# pca20035_sheet5_power_supply.net
KiCad netlist of a schematic drawn in Altium Designer
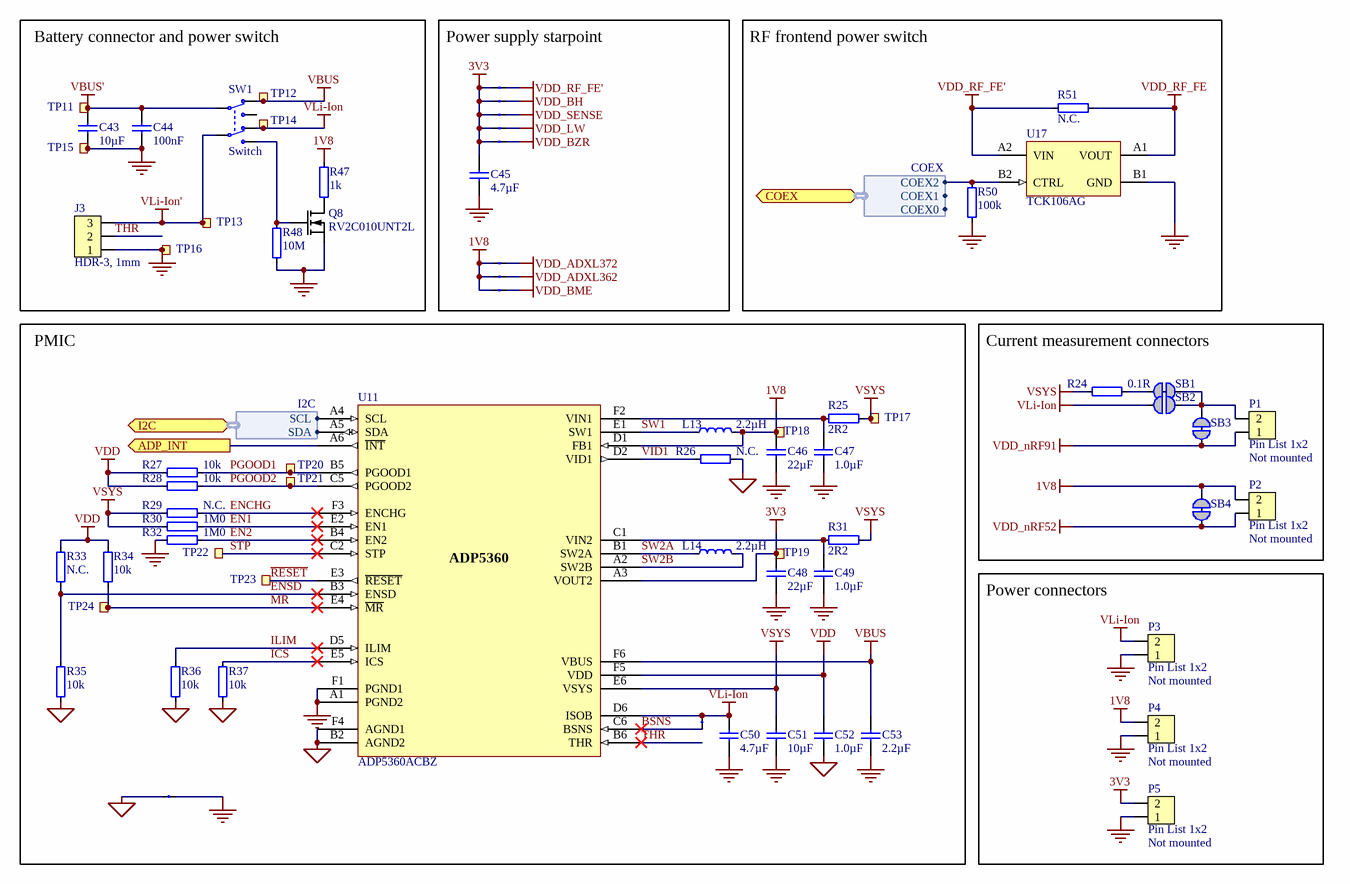
[diagram p0: pca20035_sheet5_power_supply.SchDoc]

(export (version "E")
  (design (tool "Eeschema 10.0.6"))
  (components
    (comp (ref "C43")
      (value "10µF")
      (footprint "CAPC1608X06L")
      (description "Capacitor, X5R, ±20%")
      (fields (field (name "PART NUMBER") "C0603-10µ") (field (name "MANUFACTURER") "N.A."))
      (libsource (lib "AltiumLib") (part "CAP"))
    )
    (comp (ref "C44")
      (value "100nF")
      (footprint "CAPC0603X03L_C")
      (description "Capacitor, X5R, ±10%")
      (fields (field (name "PART NUMBER") "C0201-100n") (field (name "MANUFACTURER") "N.A."))
      (libsource (lib "AltiumLib") (part "CAP"))
    )
    (comp (ref "C45")
      (value "4.7µF")
      (footprint "CAPC1608X06L")
      (description "Capacitor, X5R, ±10%")
      (fields (field (name "PART NUMBER") "C0603-4µ7") (field (name "MANUFACTURER") "N.A."))
      (libsource (lib "AltiumLib") (part "CAP"))
    )
    (comp (ref "C46")
      (value "22µF")
      (footprint "CAPC1608X06L")
      (description "Capacitor, X5R, ±20%, 6.3V")
      (fields
        (field (name "PART NUMBER") "C0603-22µ-6.3V")
        (field (name "MANUFACTURER") "Samsung Electro-Mechanics America")
      )
      (libsource (lib "AltiumLib") (part "CAP"))
    )
    (comp (ref "C47")
      (value "1.0µF")
      (footprint "CAPC1005X04L")
      (description "Capacitor, X5R, ±5%, 6.3V")
      (fields (field (name "PART NUMBER") "C0402-1µ0") (field (name "MANUFACTURER") "N.A."))
      (libsource (lib "AltiumLib") (part "CAP"))
    )
    (comp (ref "C48")
      (value "22µF")
      (footprint "CAPC1608X06L")
      (description "Capacitor, X5R, ±20%, 6.3V")
      (fields
        (field (name "PART NUMBER") "C0603-22µ-6.3V")
        (field (name "MANUFACTURER") "Samsung Electro-Mechanics America")
      )
      (libsource (lib "AltiumLib") (part "CAP"))
    )
    (comp (ref "C49")
      (value "1.0µF")
      (footprint "CAPC1608X06L")
      (description "Capacitor, X7R, ±10%")
      (fields (field (name "PART NUMBER") "C0603-1µ0") (field (name "MANUFACTURER") "N.A."))
      (libsource (lib "AltiumLib") (part "CAP"))
    )
    (comp (ref "C50")
      (value "4.7µF")
      (footprint "CAPC1608X06L")
      (description "Capacitor, X5R, ±10%")
      (fields (field (name "PART NUMBER") "C0603-4µ7") (field (name "MANUFACTURER") "N.A."))
      (libsource (lib "AltiumLib") (part "CAP"))
    )
    (comp (ref "C51")
      (value "10µF")
      (footprint "CAPC1608X06L")
      (description "Capacitor, X5R, ±20%")
      (fields (field (name "PART NUMBER") "C0603-10µ") (field (name "MANUFACTURER") "N.A."))
      (libsource (lib "AltiumLib") (part "CAP"))
    )
    (comp (ref "C52")
      (value "1.0µF")
      (footprint "CAPC1005X04L")
      (description "Capacitor, X5R, ±5%, 6.3V")
      (fields (field (name "PART NUMBER") "C0402-1µ0") (field (name "MANUFACTURER") "N.A."))
      (libsource (lib "AltiumLib") (part "CAP"))
    )
    (comp (ref "C53")
      (value "2.2µF")
      (footprint "CAPC1608X06L")
      (description "Capacitor, X7R, ±10%, 10V")
      (fields
        (field (name "PART NUMBER") "C0603-2µ2-10V")
        (field (name "MANUFACTURER") "Samsung Electro-Mechanics America")
      )
      (libsource (lib "AltiumLib") (part "CAP"))
    )
    (comp (ref "J3")
      (value "HDR-3, 1mm")
      (footprint "SM03B-SRSS-TB")
      (description "1.0mm pitch connector side entry SMD")
      (fields
        (field (name "PART NUMBER") "SM03B-SRSS-TB")
        (field (name "MANUFACTURER") "JST Sales America Inc.")
      )
      (libsource (lib "AltiumLib") (part "CONN-3"))
    )
    (comp (ref "L13")
      (value "2.2µH")
      (footprint "INDC2016X18N")
      (description "Shielded Multilayer Inductor, 1.2A, ±20%, 110mOhm, Q=10 @ 1MHz")
      (fields
        (field (name "PART NUMBER") "L0806-2µ2-1.2A-110mOhm")
        (field (name "MANUFACTURER") "Wurth Elektronik")
      )
      (libsource (lib "AltiumLib") (part "IND"))
    )
    (comp (ref "L14")
      (value "2.2µH")
      (footprint "INDC2016X18N")
      (description "Shielded Multilayer Inductor, 1.2A, ±20%, 110mOhm, Q=10 @ 1MHz")
      (fields
        (field (name "PART NUMBER") "L0806-2µ2-1.2A-110mOhm")
        (field (name "MANUFACTURER") "Wurth Elektronik")
      )
      (libsource (lib "AltiumLib") (part "IND"))
    )
    (comp (ref "P1")
      (value "Pin List 1x2")
      (footprint "LIST_1x2-NC")
      (description "Pin List 1x2, 2.54mm (100mil)")
      (fields
        (field (name "PART NUMBER") "Pin List 1x2, N.C.")
        (field (name "ASSEMBLY") "Not mounted")
        (field (name "MANUFACTURER") "N.A.")
      )
      (libsource (lib "AltiumLib") (part "CONN-2"))
    )
    (comp (ref "P2")
      (value "Pin List 1x2")
      (footprint "LIST_1x2-NC")
      (description "Pin List 1x2, 2.54mm (100mil)")
      (fields
        (field (name "PART NUMBER") "Pin List 1x2, N.C.")
        (field (name "ASSEMBLY") "Not mounted")
        (field (name "MANUFACTURER") "N.A.")
      )
      (libsource (lib "AltiumLib") (part "CONN-2"))
    )
    (comp (ref "P3")
      (value "Pin List 1x2")
      (footprint "LIST_1x2-NC")
      (description "Pin List 1x2, 2.54mm (100mil)")
      (fields
        (field (name "PART NUMBER") "Pin List 1x2, N.C.")
        (field (name "ASSEMBLY") "Not mounted")
        (field (name "MANUFACTURER") "N.A.")
      )
      (libsource (lib "AltiumLib") (part "CONN-2"))
    )
    (comp (ref "P4")
      (value "Pin List 1x2")
      (footprint "LIST_1x2-NC")
      (description "Pin List 1x2, 2.54mm (100mil)")
      (fields
        (field (name "PART NUMBER") "Pin List 1x2, N.C.")
        (field (name "ASSEMBLY") "Not mounted")
        (field (name "MANUFACTURER") "N.A.")
      )
      (libsource (lib "AltiumLib") (part "CONN-2"))
    )
    (comp (ref "P5")
      (value "Pin List 1x2")
      (footprint "LIST_1x2-NC")
      (description "Pin List 1x2, 2.54mm (100mil)")
      (fields
        (field (name "PART NUMBER") "Pin List 1x2, N.C.")
        (field (name "ASSEMBLY") "Not mounted")
        (field (name "MANUFACTURER") "N.A.")
      )
      (libsource (lib "AltiumLib") (part "CONN-2"))
    )
    (comp (ref "Q8")
      (value "RV2C010UNT2L")
      (footprint "DFN65P100X40-3L")
      (description "N-Channel MOSFET, 20V, 1A, 470mOhm, 400mW")
      (fields (field (name "MANUFACTURER") "Rohm Semiconductor"))
      (libsource (lib "AltiumLib") (part "T{colon}FET-N"))
    )
    (comp (ref "R24")
      (value "0.1R")
      (footprint "RESC1005X04L")
      (description "Resistor, ±1%, 0.063W")
      (fields (field (name "PART NUMBER") "R0402-0R1") (field (name "MANUFACTURER") "N.A."))
      (libsource (lib "AltiumLib") (part "RES"))
    )
    (comp (ref "R25")
      (value "2R2")
      (footprint "RESC1005X04L")
      (description "Resistor, ±1%, 0.063W")
      (fields (field (name "PART NUMBER") "R0402-2R2") (field (name "MANUFACTURER") "N.A."))
      (libsource (lib "AltiumLib") (part "RES"))
    )
    (comp (ref "R26")
      (value "N.C.")
      (footprint "RESC0603X03L_C_NC")
      (description "Not mounted")
      (fields (field (name "PART NUMBER") "R0201-N.C.") (field (name "MANUFACTURER") "N.A."))
      (libsource (lib "AltiumLib") (part "RES"))
    )
    (comp (ref "R27")
      (value "10k")
      (footprint "RESC0603X03L_C")
      (description "Resistor, ±1%, 0.05W")
      (fields (field (name "PART NUMBER") "R0201-10k") (field (name "MANUFACTURER") "N.A."))
      (libsource (lib "AltiumLib") (part "RES"))
    )
    (comp (ref "R28")
      (value "10k")
      (footprint "RESC0603X03L_C")
      (description "Resistor, ±1%, 0.05W")
      (fields (field (name "PART NUMBER") "R0201-10k") (field (name "MANUFACTURER") "N.A."))
      (libsource (lib "AltiumLib") (part "RES"))
    )
    (comp (ref "R29")
      (value "N.C.")
      (footprint "RESC0603X03L_C_NC")
      (description "Not mounted")
      (fields (field (name "PART NUMBER") "R0201-N.C.") (field (name "MANUFACTURER") "N.A."))
      (libsource (lib "AltiumLib") (part "RES"))
    )
    (comp (ref "R30")
      (value "1M0")
      (footprint "RESC0603X03L_C")
      (description "Resistor, ±1%, 0.05W")
      (fields (field (name "PART NUMBER") "R0201-1M0") (field (name "MANUFACTURER") "N.A."))
      (libsource (lib "AltiumLib") (part "RES"))
    )
    (comp (ref "R31")
      (value "2R2")
      (footprint "RESC1005X04L")
      (description "Resistor, ±1%, 0.063W")
      (fields (field (name "PART NUMBER") "R0402-2R2") (field (name "MANUFACTURER") "N.A."))
      (libsource (lib "AltiumLib") (part "RES"))
    )
    (comp (ref "R32")
      (value "1M0")
      (footprint "RESC0603X03L_C")
      (description "Resistor, ±1%, 0.05W")
      (fields (field (name "PART NUMBER") "R0201-1M0") (field (name "MANUFACTURER") "N.A."))
      (libsource (lib "AltiumLib") (part "RES"))
    )
    (comp (ref "R33")
      (value "N.C.")
      (footprint "RESC0603X03L_C_NC")
      (description "Not mounted")
      (fields (field (name "PART NUMBER") "R0201-N.C.") (field (name "MANUFACTURER") "N.A."))
      (libsource (lib "AltiumLib") (part "RES"))
    )
    (comp (ref "R34")
      (value "10k")
      (footprint "RESC0603X03L_C")
      (description "Resistor, ±1%, 0.05W")
      (fields (field (name "PART NUMBER") "R0201-10k") (field (name "MANUFACTURER") "N.A."))
      (libsource (lib "AltiumLib") (part "RES"))
    )
    (comp (ref "R35")
      (value "10k")
      (footprint "RESC0603X03L_C")
      (description "Resistor, ±1%, 0.05W")
      (fields (field (name "PART NUMBER") "R0201-10k") (field (name "MANUFACTURER") "N.A."))
      (libsource (lib "AltiumLib") (part "RES"))
    )
    (comp (ref "R36")
      (value "10k")
      (footprint "RESC0603X03L_C")
      (description "Resistor, ±1%, 0.05W")
      (fields (field (name "PART NUMBER") "R0201-10k") (field (name "MANUFACTURER") "N.A."))
      (libsource (lib "AltiumLib") (part "RES"))
    )
    (comp (ref "R37")
      (value "10k")
      (footprint "RESC0603X03L_C")
      (description "Resistor, ±1%, 0.05W")
      (fields (field (name "PART NUMBER") "R0201-10k") (field (name "MANUFACTURER") "N.A."))
      (libsource (lib "AltiumLib") (part "RES"))
    )
    (comp (ref "R47")
      (value "1k")
      (footprint "RESC0603X03L_C")
      (description "Resistor, ±1%, 0.05W")
      (fields (field (name "PART NUMBER") "R0201-1k0") (field (name "MANUFACTURER") "N.A."))
      (libsource (lib "AltiumLib") (part "RES"))
    )
    (comp (ref "R48")
      (value "10M")
      (footprint "RESC0603X03L_C")
      (description "Resistor, ±1%, 0.05W")
      (fields (field (name "PART NUMBER") "R0201-10M") (field (name "MANUFACTURER") "N.A."))
      (libsource (lib "AltiumLib") (part "RES"))
    )
    (comp (ref "R50")
      (value "100k")
      (footprint "RESC0603X03L_C")
      (description "Resistor, ±1%, 0.05W")
      (fields (field (name "PART NUMBER") "R0201-100k") (field (name "MANUFACTURER") "N.A."))
      (libsource (lib "AltiumLib") (part "RES"))
    )
    (comp (ref "R51")
      (value "N.C.")
      (footprint "RESC0603X03L_C_NC")
      (description "Not mounted")
      (fields (field (name "PART NUMBER") "R0201-N.C.") (field (name "MANUFACTURER") "N.A."))
      (libsource (lib "AltiumLib") (part "RES"))
    )
    (comp (ref "SB1")
      (value "Solderbridge")
      (footprint "Solderbridge_Shorted")
      (description "Shorted Solderbridge")
      (fields (field (name "PART NUMBER") "Solderbridge Shorted") (field (name "MANUFACTURER") "N.A."))
      (libsource (lib "AltiumLib") (part "SOLDERBRIDGE_SHORTED"))
    )
    (comp (ref "SB2")
      (value "Solderbridge")
      (footprint "Solderbridge")
      (fields (field (name "MANUFACTURER") "N.A."))
      (libsource (lib "AltiumLib") (part "SOLDERBRIDGE"))
    )
    (comp (ref "SB3")
      (value "Solderbridge")
      (footprint "Solderbridge_Shorted")
      (description "Shorted Solderbridge")
      (fields (field (name "PART NUMBER") "Solderbridge Shorted") (field (name "MANUFACTURER") "N.A."))
      (libsource (lib "AltiumLib") (part "SOLDERBRIDGE_SHORTED"))
    )
    (comp (ref "SB4")
      (value "Solderbridge")
      (footprint "Solderbridge_Shorted")
      (description "Shorted Solderbridge")
      (fields (field (name "PART NUMBER") "Solderbridge Shorted") (field (name "MANUFACTURER") "N.A."))
      (libsource (lib "AltiumLib") (part "SOLDERBRIDGE_SHORTED"))
    )
    (comp (ref "ST1")
      (value "N.A.")
      (footprint "2 PIN STARPOINT")
      (description "Starpoint")
      (fields (field (name "PART NUMBER") "2 pin starpoint"))
      (libsource (lib "AltiumLib") (part "2 pin starpoint"))
    )
    (comp (ref "ST2")
      (value "N.A.")
      (footprint "2 PIN STARPOINT")
      (description "Starpoint")
      (fields (field (name "PART NUMBER") "2 pin starpoint"))
      (libsource (lib "AltiumLib") (part "2 pin starpoint"))
    )
    (comp (ref "ST3")
      (value "N.A.")
      (footprint "2 PIN STARPOINT")
      (description "Starpoint")
      (fields (field (name "PART NUMBER") "2 pin starpoint"))
      (libsource (lib "AltiumLib") (part "2 pin starpoint"))
    )
    (comp (ref "ST4")
      (value "N.A.")
      (footprint "2 PIN STARPOINT")
      (description "Starpoint")
      (fields (field (name "PART NUMBER") "2 pin starpoint"))
      (libsource (lib "AltiumLib") (part "2 pin starpoint"))
    )
    (comp (ref "ST5")
      (value "N.A.")
      (footprint "2 PIN STARPOINT")
      (description "Starpoint")
      (fields (field (name "PART NUMBER") "2 pin starpoint"))
      (libsource (lib "AltiumLib") (part "2 pin starpoint"))
    )
    (comp (ref "ST7")
      (value "N.A.")
      (footprint "2 PIN STARPOINT")
      (description "Starpoint")
      (fields (field (name "PART NUMBER") "2 pin starpoint"))
      (libsource (lib "AltiumLib") (part "2 pin starpoint"))
    )
    (comp (ref "ST8")
      (value "N.A.")
      (footprint "2 PIN STARPOINT")
      (description "Starpoint")
      (fields (field (name "PART NUMBER") "2 pin starpoint"))
      (libsource (lib "AltiumLib") (part "2 pin starpoint"))
    )
    (comp (ref "ST9")
      (value "N.A.")
      (footprint "2 PIN STARPOINT")
      (description "Starpoint")
      (fields (field (name "PART NUMBER") "2 pin starpoint"))
      (libsource (lib "AltiumLib") (part "2 pin starpoint"))
    )
    (comp (ref "ST10")
      (value "N.A.")
      (footprint "2 PIN STARPOINT")
      (description "Starpoint")
      (fields (field (name "PART NUMBER") "2 pin starpoint"))
      (libsource (lib "AltiumLib") (part "2 pin starpoint"))
    )
    (comp (ref "ST11")
      (value "N.A.")
      (footprint "2 PIN STARPOINT")
      (description "Starpoint")
      (fields (field (name "PART NUMBER") "2 pin starpoint"))
      (libsource (lib "AltiumLib") (part "2 pin starpoint"))
    )
    (comp (ref "SW1")
      (value "Switch")
      (footprint "Switch-Slide-RA-J-Lead-DPDT-8.5x3.5mm")
      (description "SMD slide Switch (ON-ON)")
      (fields
        (field (name "PART NUMBER") "Switch-Slide-RA-J-Lead-DPDT-8.5x3.5mm_Copal")
        (field (name "MANUFACTURER") "Copal Electronics Inc")
      )
      (libsource (lib "AltiumLib") (part "SW-DPDT"))
    )
    (comp (ref "TP11")
      (value "Ø1.5mm,SMD")
      (footprint "TP_SMD_Ø1.5mm")
      (description "1.5mm circular SMD testpad")
      (fields
        (field (name "PART NUMBER") "TP_SMD_Ø1.5MM")
        (field (name "MANUFACTURER") "Nordic Semiconductor")
      )
      (libsource (lib "AltiumLib") (part "TESTPAD"))
    )
    (comp (ref "TP12")
      (value "Ø1.5mm,SMD")
      (footprint "TP_SMD_Ø1.5mm")
      (description "1.5mm circular SMD testpad")
      (fields
        (field (name "PART NUMBER") "TP_SMD_Ø1.5MM")
        (field (name "MANUFACTURER") "Nordic Semiconductor")
      )
      (libsource (lib "") (part "TESTPAD_2"))
    )
    (comp (ref "TP13")
      (value "Ø1.5mm,SMD")
      (footprint "TP_SMD_Ø1.5mm")
      (description "1.5mm circular SMD testpad")
      (fields
        (field (name "PART NUMBER") "TP_SMD_Ø1.5MM")
        (field (name "MANUFACTURER") "Nordic Semiconductor")
      )
      (libsource (lib "") (part "TESTPAD_1"))
    )
    (comp (ref "TP14")
      (value "Ø1.5mm,SMD")
      (footprint "TP_SMD_Ø1.5mm")
      (description "1.5mm circular SMD testpad")
      (fields
        (field (name "PART NUMBER") "TP_SMD_Ø1.5MM")
        (field (name "MANUFACTURER") "Nordic Semiconductor")
      )
      (libsource (lib "") (part "TESTPAD_2"))
    )
    (comp (ref "TP15")
      (value "Ø1.5mm,SMD")
      (footprint "TP_SMD_Ø1.5mm")
      (description "1.5mm circular SMD testpad")
      (fields
        (field (name "PART NUMBER") "TP_SMD_Ø1.5MM")
        (field (name "MANUFACTURER") "Nordic Semiconductor")
      )
      (libsource (lib "AltiumLib") (part "TESTPAD"))
    )
    (comp (ref "TP16")
      (value "Ø1.5mm,SMD")
      (footprint "TP_SMD_Ø1.5mm")
      (description "1.5mm circular SMD testpad")
      (fields
        (field (name "PART NUMBER") "TP_SMD_Ø1.5MM")
        (field (name "MANUFACTURER") "Nordic Semiconductor")
      )
      (libsource (lib "") (part "TESTPAD_1"))
    )
    (comp (ref "TP17")
      (value "Ø1.5mm,SMD")
      (footprint "TP_SMD_Ø1.5mm")
      (description "1.5mm circular SMD testpad")
      (fields
        (field (name "PART NUMBER") "TP_SMD_Ø1.5MM")
        (field (name "MANUFACTURER") "Nordic Semiconductor")
      )
      (libsource (lib "") (part "TESTPAD_2"))
    )
    (comp (ref "TP18")
      (value "Ø1.5mm,SMD")
      (footprint "TP_SMD_Ø1.5mm")
      (description "1.5mm circular SMD testpad")
      (fields
        (field (name "PART NUMBER") "TP_SMD_Ø1.5MM")
        (field (name "MANUFACTURER") "Nordic Semiconductor")
      )
      (libsource (lib "") (part "TESTPAD_1"))
    )
    (comp (ref "TP19")
      (value "Ø1.5mm,SMD")
      (footprint "TP_SMD_Ø1.5mm")
      (description "1.5mm circular SMD testpad")
      (fields
        (field (name "PART NUMBER") "TP_SMD_Ø1.5MM")
        (field (name "MANUFACTURER") "Nordic Semiconductor")
      )
      (libsource (lib "") (part "TESTPAD_1"))
    )
    (comp (ref "TP20")
      (value "Ø1.5mm,SMD")
      (footprint "TP_SMD_Ø1.5mm")
      (description "1.5mm circular SMD testpad")
      (fields
        (field (name "PART NUMBER") "TP_SMD_Ø1.5MM")
        (field (name "MANUFACTURER") "Nordic Semiconductor")
      )
      (libsource (lib "") (part "TESTPAD_2"))
    )
    (comp (ref "TP21")
      (value "Ø1.5mm,SMD")
      (footprint "TP_SMD_Ø1.5mm")
      (description "1.5mm circular SMD testpad")
      (fields
        (field (name "PART NUMBER") "TP_SMD_Ø1.5MM")
        (field (name "MANUFACTURER") "Nordic Semiconductor")
      )
      (libsource (lib "") (part "TESTPAD_2"))
    )
    (comp (ref "TP22")
      (value "Ø1.0mm,SMD")
      (footprint "TP_SMD_Ø1.0mm")
      (description "1.0mm circular SMD testpad")
      (fields
        (field (name "PART NUMBER") "TP_SMD_Ø1.0MM")
        (field (name "MANUFACTURER") "Nordic Semiconductor")
      )
      (libsource (lib "AltiumLib") (part "TESTPAD"))
    )
    (comp (ref "TP23")
      (value "Ø1.0mm,SMD")
      (footprint "TP_SMD_Ø1.0mm")
      (description "1.0mm circular SMD testpad")
      (fields
        (field (name "PART NUMBER") "TP_SMD_Ø1.0MM")
        (field (name "MANUFACTURER") "Nordic Semiconductor")
      )
      (libsource (lib "AltiumLib") (part "TESTPAD"))
    )
    (comp (ref "TP24")
      (value "Ø1.0mm,SMD")
      (footprint "TP_SMD_Ø1.0mm")
      (description "1.0mm circular SMD testpad")
      (fields
        (field (name "PART NUMBER") "TP_SMD_Ø1.0MM")
        (field (name "MANUFACTURER") "Nordic Semiconductor")
      )
      (libsource (lib "AltiumLib") (part "TESTPAD"))
    )
    (comp (ref "U11")
      (value "ADP5360ACBZ")
      (footprint "BGA32C40P6X6_238X238X56")
      (description "Advanced Battery Management PMIC With Ultralow Iq Buck and Buck-Boost")
      (fields (field (name "MANUFACTURER") "Analog Devices"))
      (libsource (lib "AltiumLib") (part "ADP5360ACBZ"))
    )
    (comp (ref "U17")
      (value "TCK106AG")
      (footprint "BGA4C40P2X2_76X76X62")
      (description "1.0 A Load Switch IC with Slew Rate Control Driver in Ultra Small Package")
      (fields (field (name "MANUFACTURER") "Toshiba") (field (name "MANUFACTURER PART NUMBER") "TCK106AG,LF"))
      (libsource (lib "AltiumLib") (part "TCK106AG"))
    )
  )
  (nets
    (net (code "3") (name "/ADP_INT") (class "Default")
      (node (ref "U11") (pin "A6") (pinfunction "~{INT}_A6") (pintype "output"))
    )
    (net (code "4") (name "/BSNS") (class "Default")
      (node (ref "ST10") (pin "1") (pintype "passive"))
      (node (ref "U11") (pin "C6") (pinfunction "BSNS_C6") (pintype "input"))
    )
    (net (code "5") (name "/COEX2") (class "Default")
      (node (ref "R50") (pin "2") (pinfunction "2_2") (pintype "passive"))
      (node (ref "U17") (pin "B2") (pinfunction "CTRL_B2") (pintype "input"))
    )
    (net (code "6") (name "/EN1") (class "Default")
      (node (ref "R30") (pin "2") (pinfunction "2_2") (pintype "passive"))
      (node (ref "U11") (pin "E2") (pinfunction "EN1_E2") (pintype "input"))
    )
    (net (code "7") (name "/EN2") (class "Default")
      (node (ref "R32") (pin "2") (pinfunction "2_2") (pintype "passive"))
      (node (ref "U11") (pin "B4") (pinfunction "EN2_B4") (pintype "input"))
    )
    (net (code "8") (name "/ENCHG") (class "Default")
      (node (ref "R29") (pin "2") (pinfunction "2_2") (pintype "passive"))
      (node (ref "U11") (pin "F3") (pinfunction "ENCHG_F3") (pintype "input"))
    )
    (net (code "9") (name "/ENSD") (class "Default")
      (node (ref "R33") (pin "1") (pinfunction "1_1") (pintype "passive"))
      (node (ref "R35") (pin "2") (pinfunction "2_2") (pintype "passive"))
      (node (ref "U11") (pin "B3") (pinfunction "ENSD_B3") (pintype "input"))
    )
    (net (code "10") (name "/ICS") (class "Default")
      (node (ref "R37") (pin "1") (pinfunction "1_1") (pintype "passive"))
      (node (ref "U11") (pin "E5") (pinfunction "ICS_E5") (pintype "input"))
    )
    (net (code "11") (name "/ILIM") (class "Default")
      (node (ref "R36") (pin "1") (pinfunction "1_1") (pintype "passive"))
      (node (ref "U11") (pin "D5") (pinfunction "ILIM_D5") (pintype "input"))
    )
    (net (code "12") (name "/PGOOD1") (class "Default")
      (node (ref "R27") (pin "2") (pinfunction "2_2") (pintype "passive"))
      (node (ref "TP20") (pin "1") (pinfunction "1_1") (pintype "passive"))
      (node (ref "U11") (pin "B5") (pinfunction "PGOOD1_B5") (pintype "output"))
    )
    (net (code "13") (name "/PGOOD2") (class "Default")
      (node (ref "R28") (pin "2") (pinfunction "2_2") (pintype "passive"))
      (node (ref "TP21") (pin "1") (pinfunction "1_1") (pintype "passive"))
      (node (ref "U11") (pin "C5") (pinfunction "PGOOD2_C5") (pintype "output"))
    )
    (net (code "14") (name "/SCL") (class "Default")
      (node (ref "U11") (pin "A4") (pinfunction "SCL_A4") (pintype "input"))
    )
    (net (code "15") (name "/SDA") (class "Default")
      (node (ref "U11") (pin "A5") (pinfunction "SDA_A5") (pintype "bidirectional"))
    )
    (net (code "16") (name "/STP") (class "Default")
      (node (ref "TP22") (pin "1") (pinfunction "1_1") (pintype "passive"))
      (node (ref "U11") (pin "C2") (pinfunction "STP_C2") (pintype "input"))
    )
    (net (code "17") (name "/SW1") (class "Default")
      (node (ref "L13") (pin "1") (pinfunction "1_1") (pintype "passive"))
      (node (ref "U11") (pin "E1") (pinfunction "SW1_E1") (pintype "power_in"))
    )
    (net (code "18") (name "/SW2A") (class "Default")
      (node (ref "L14") (pin "1") (pinfunction "1_1") (pintype "passive"))
      (node (ref "U11") (pin "B1") (pinfunction "SW2A_B1") (pintype "power_in"))
    )
    (net (code "19") (name "/SW2B") (class "Default")
      (node (ref "L14") (pin "2") (pinfunction "2_2") (pintype "passive"))
      (node (ref "U11") (pin "A2") (pinfunction "SW2B_A2") (pintype "power_in"))
    )
    (net (code "20") (name "/THR") (class "Default")
      (node (ref "J3") (pin "2") (pinfunction "2_2") (pintype "passive"))
      (node (ref "U11") (pin "B6") (pinfunction "THR_B6") (pintype "input"))
    )
    (net (code "21") (name "/VID1") (class "Default")
      (node (ref "R26") (pin "1") (pinfunction "1_1") (pintype "passive"))
      (node (ref "U11") (pin "D2") (pinfunction "VID1_D2") (pintype "output"))
    )
    (net (code "24") (name "/~{MR}") (class "Default")
      (node (ref "R34") (pin "2") (pinfunction "2_2") (pintype "passive"))
      (node (ref "TP24") (pin "1") (pinfunction "1_1") (pintype "passive"))
      (node (ref "U11") (pin "E4") (pinfunction "~{MR}_E4") (pintype "input"))
    )
    (net (code "25") (name "/~{RESET}") (class "Default")
      (node (ref "TP23") (pin "1") (pinfunction "1_1") (pintype "passive"))
      (node (ref "U11") (pin "E3") (pinfunction "~{RESET}_E3") (pintype "output"))
    )
    (net (code "26") (name "1V8") (class "Default")
      (node (ref "C46") (pin "2") (pinfunction "2_2") (pintype "passive"))
      (node (ref "L13") (pin "2") (pinfunction "2_2") (pintype "passive"))
      (node (ref "P2") (pin "2") (pinfunction "2_2") (pintype "passive"))
      (node (ref "P4") (pin "2") (pinfunction "2_2") (pintype "passive"))
      (node (ref "R47") (pin "1") (pinfunction "1_1") (pintype "passive"))
      (node (ref "SB4") (pin "2") (pinfunction "1_2") (pintype "passive"))
      (node (ref "ST7") (pin "1") (pintype "passive"))
      (node (ref "ST8") (pin "1") (pintype "passive"))
      (node (ref "ST9") (pin "1") (pintype "passive"))
      (node (ref "TP18") (pin "1") (pinfunction "1_1") (pintype "passive"))
      (node (ref "U11") (pin "D1") (pinfunction "FB1_D1") (pintype "input"))
    )
    (net (code "27") (name "3V3") (class "Default")
      (node (ref "C45") (pin "2") (pinfunction "2_2") (pintype "passive"))
      (node (ref "C48") (pin "2") (pinfunction "2_2") (pintype "passive"))
      (node (ref "P5") (pin "2") (pinfunction "2_2") (pintype "passive"))
      (node (ref "ST1") (pin "1") (pintype "passive"))
      (node (ref "ST2") (pin "1") (pintype "passive"))
      (node (ref "ST3") (pin "1") (pintype "passive"))
      (node (ref "ST4") (pin "1") (pintype "passive"))
      (node (ref "ST5") (pin "1") (pintype "passive"))
      (node (ref "TP19") (pin "1") (pinfunction "1_1") (pintype "passive"))
      (node (ref "U11") (pin "A3") (pinfunction "VOUT2_A3") (pintype "power_in"))
    )
    (net (code "28") (name "AGND") (class "Default")
      (node (ref "C52") (pin "1") (pinfunction "1_1") (pintype "passive"))
      (node (ref "R26") (pin "2") (pinfunction "2_2") (pintype "passive"))
      (node (ref "R35") (pin "1") (pinfunction "1_1") (pintype "passive"))
      (node (ref "R36") (pin "2") (pinfunction "2_2") (pintype "passive"))
      (node (ref "R37") (pin "2") (pinfunction "2_2") (pintype "passive"))
      (node (ref "ST11") (pin "1") (pintype "passive"))
      (node (ref "U11") (pin "B2") (pinfunction "AGND2_B2") (pintype "power_in"))
      (node (ref "U11") (pin "F4") (pinfunction "AGND1_F4") (pintype "power_in"))
    )
    (net (code "29") (name "GND") (class "Default")
      (node (ref "C43") (pin "2") (pinfunction "2_2") (pintype "passive"))
      (node (ref "C44") (pin "2") (pinfunction "2_2") (pintype "passive"))
      (node (ref "C45") (pin "1") (pinfunction "1_1") (pintype "passive"))
      (node (ref "C46") (pin "1") (pinfunction "1_1") (pintype "passive"))
      (node (ref "C47") (pin "1") (pinfunction "1_1") (pintype "passive"))
      (node (ref "C48") (pin "1") (pinfunction "1_1") (pintype "passive"))
      (node (ref "C49") (pin "1") (pinfunction "1_1") (pintype "passive"))
      (node (ref "C50") (pin "1") (pinfunction "1_1") (pintype "passive"))
      (node (ref "C51") (pin "1") (pinfunction "1_1") (pintype "passive"))
      (node (ref "C53") (pin "1") (pinfunction "1_1") (pintype "passive"))
      (node (ref "J3") (pin "1") (pinfunction "1_1") (pintype "passive"))
      (node (ref "P3") (pin "1") (pinfunction "1_1") (pintype "passive"))
      (node (ref "P4") (pin "1") (pinfunction "1_1") (pintype "passive"))
      (node (ref "P5") (pin "1") (pinfunction "1_1") (pintype "passive"))
      (node (ref "Q8") (pin "2") (pinfunction "S_2") (pintype "passive"))
      (node (ref "R32") (pin "1") (pinfunction "1_1") (pintype "passive"))
      (node (ref "R48") (pin "2") (pinfunction "2_2") (pintype "passive"))
      (node (ref "R50") (pin "1") (pinfunction "1_1") (pintype "passive"))
      (node (ref "ST11") (pin "2") (pintype "passive"))
      (node (ref "TP15") (pin "1") (pinfunction "1_1") (pintype "passive"))
      (node (ref "TP16") (pin "1") (pinfunction "1_1") (pintype "passive"))
      (node (ref "U11") (pin "A1") (pinfunction "PGND2_A1") (pintype "power_in"))
      (node (ref "U11") (pin "F1") (pinfunction "PGND1_F1") (pintype "power_in"))
      (node (ref "U17") (pin "B1") (pinfunction "GND_B1") (pintype "power_in"))
    )
    (net (code "30") (name "Net-(Q8-D)") (class "Default")
      (node (ref "Q8") (pin "3") (pinfunction "D_3") (pintype "passive"))
      (node (ref "R47") (pin "2") (pinfunction "2_2") (pintype "passive"))
    )
    (net (code "31") (name "Net-(Q8-G)") (class "Default")
      (node (ref "Q8") (pin "1") (pinfunction "G_1") (pintype "passive"))
      (node (ref "R48") (pin "1") (pinfunction "1_1") (pintype "passive"))
      (node (ref "SW1") (pin "4") (pinfunction "N.O-2_4") (pintype "passive"))
    )
    (net (code "32") (name "Net-(SB1-0)") (class "Default")
      (node (ref "P1") (pin "2") (pinfunction "2_2") (pintype "passive"))
      (node (ref "SB1") (pin "1") (pinfunction "0_1") (pintype "passive"))
      (node (ref "SB2") (pin "1") (pinfunction "0_1") (pintype "passive"))
      (node (ref "SB3") (pin "2") (pinfunction "1_2") (pintype "passive"))
    )
    (net (code "33") (name "Net-(SB1-1)") (class "Default")
      (node (ref "R24") (pin "1") (pinfunction "1_1") (pintype "passive"))
      (node (ref "SB1") (pin "2") (pinfunction "1_2") (pintype "passive"))
    )
    (net (code "34") (name "Net-(U11-VIN1)") (class "Default")
      (node (ref "C47") (pin "2") (pinfunction "2_2") (pintype "passive"))
      (node (ref "R25") (pin "1") (pinfunction "1_1") (pintype "passive"))
      (node (ref "U11") (pin "F2") (pinfunction "VIN1_F2") (pintype "power_in"))
    )
    (net (code "35") (name "Net-(U11-VIN2)") (class "Default")
      (node (ref "C49") (pin "2") (pinfunction "2_2") (pintype "passive"))
      (node (ref "R31") (pin "1") (pinfunction "1_1") (pintype "passive"))
      (node (ref "U11") (pin "C1") (pinfunction "VIN2_C1") (pintype "power_in"))
    )
    (net (code "36") (name "VBUS") (class "Default")
      (node (ref "C53") (pin "2") (pinfunction "2_2") (pintype "passive"))
      (node (ref "SW1") (pin "3") (pinfunction "N.C-1_3") (pintype "passive"))
      (node (ref "TP12") (pin "1") (pinfunction "1_1") (pintype "passive"))
      (node (ref "U11") (pin "F6") (pinfunction "VBUS_F6") (pintype "power_in"))
    )
    (net (code "37") (name "VBUS'") (class "Default")
      (node (ref "C43") (pin "1") (pinfunction "1_1") (pintype "passive"))
      (node (ref "C44") (pin "1") (pinfunction "1_1") (pintype "passive"))
      (node (ref "SW1") (pin "2") (pinfunction "COM-1_2") (pintype "passive"))
      (node (ref "TP11") (pin "1") (pinfunction "1_1") (pintype "passive"))
    )
    (net (code "38") (name "VDD") (class "Default")
      (node (ref "C52") (pin "2") (pinfunction "2_2") (pintype "passive"))
      (node (ref "R27") (pin "1") (pinfunction "1_1") (pintype "passive"))
      (node (ref "R28") (pin "1") (pinfunction "1_1") (pintype "passive"))
      (node (ref "R33") (pin "2") (pinfunction "2_2") (pintype "passive"))
      (node (ref "R34") (pin "1") (pinfunction "1_1") (pintype "passive"))
      (node (ref "U11") (pin "F5") (pinfunction "VDD_F5") (pintype "power_in"))
    )
    (net (code "39") (name "VDD_ADXL362") (class "Default") (node (ref "ST8") (pin "2") (pintype "passive")))
    (net (code "40") (name "VDD_ADXL372") (class "Default") (node (ref "ST7") (pin "2") (pintype "passive")))
    (net (code "41") (name "VDD_BH") (class "Default") (node (ref "ST2") (pin "2") (pintype "passive")))
    (net (code "42") (name "VDD_BME") (class "Default") (node (ref "ST9") (pin "2") (pintype "passive")))
    (net (code "43") (name "VDD_BZR") (class "Default") (node (ref "ST5") (pin "2") (pintype "passive")))
    (net (code "44") (name "VDD_LW") (class "Default") (node (ref "ST4") (pin "2") (pintype "passive")))
    (net (code "45") (name "VDD_RF_FE") (class "Default")
      (node (ref "R51") (pin "1") (pinfunction "1_1") (pintype "passive"))
      (node (ref "U17") (pin "A1") (pinfunction "VOUT_A1") (pintype "power_in"))
    )
    (net (code "46") (name "VDD_RF_FE'") (class "Default")
      (node (ref "R51") (pin "2") (pinfunction "2_2") (pintype "passive"))
      (node (ref "ST1") (pin "2") (pintype "passive"))
      (node (ref "U17") (pin "A2") (pinfunction "VIN_A2") (pintype "power_in"))
    )
    (net (code "47") (name "VDD_SENSE") (class "Default") (node (ref "ST3") (pin "2") (pintype "passive")))
    (net (code "48") (name "VDD_nRF52") (class "Default")
      (node (ref "P2") (pin "1") (pinfunction "1_1") (pintype "passive"))
      (node (ref "SB4") (pin "1") (pinfunction "0_1") (pintype "passive"))
    )
    (net (code "49") (name "VDD_nRF91") (class "Default")
      (node (ref "P1") (pin "1") (pinfunction "1_1") (pintype "passive"))
      (node (ref "SB3") (pin "1") (pinfunction "0_1") (pintype "passive"))
    )
    (net (code "50") (name "VLi-Ion") (class "Default")
      (node (ref "C50") (pin "2") (pinfunction "2_2") (pintype "passive"))
      (node (ref "P3") (pin "2") (pinfunction "2_2") (pintype "passive"))
      (node (ref "SB2") (pin "2") (pinfunction "1_2") (pintype "passive"))
      (node (ref "ST10") (pin "2") (pintype "passive"))
      (node (ref "SW1") (pin "6") (pinfunction "N.C-2_6") (pintype "passive"))
      (node (ref "TP14") (pin "1") (pinfunction "1_1") (pintype "passive"))
      (node (ref "U11") (pin "D6") (pinfunction "ISOB_D6") (pintype "power_in"))
    )
    (net (code "51") (name "VLi-Ion'") (class "Default")
      (node (ref "J3") (pin "3") (pinfunction "3_3") (pintype "passive"))
      (node (ref "SW1") (pin "5") (pinfunction "COM-2_5") (pintype "passive"))
      (node (ref "TP13") (pin "1") (pinfunction "1_1") (pintype "passive"))
    )
    (net (code "52") (name "VSYS") (class "Default")
      (node (ref "C51") (pin "2") (pinfunction "2_2") (pintype "passive"))
      (node (ref "R24") (pin "2") (pinfunction "2_2") (pintype "passive"))
      (node (ref "R25") (pin "2") (pinfunction "2_2") (pintype "passive"))
      (node (ref "R29") (pin "1") (pinfunction "1_1") (pintype "passive"))
      (node (ref "R30") (pin "1") (pinfunction "1_1") (pintype "passive"))
      (node (ref "R31") (pin "2") (pinfunction "2_2") (pintype "passive"))
      (node (ref "TP17") (pin "1") (pinfunction "1_1") (pintype "passive"))
      (node (ref "U11") (pin "E6") (pinfunction "VSYS_E6") (pintype "power_in"))
    )
    (net (code "53") (name "unconnected-(SW1-N.O-1-Pad1)") (class "Default")
      (node (ref "SW1") (pin "1") (pinfunction "N.O-1_1") (pintype "passive"))
    )
  )
)
